# power-input.net
KiCad netlist of a schematic drawn in Altium Designer
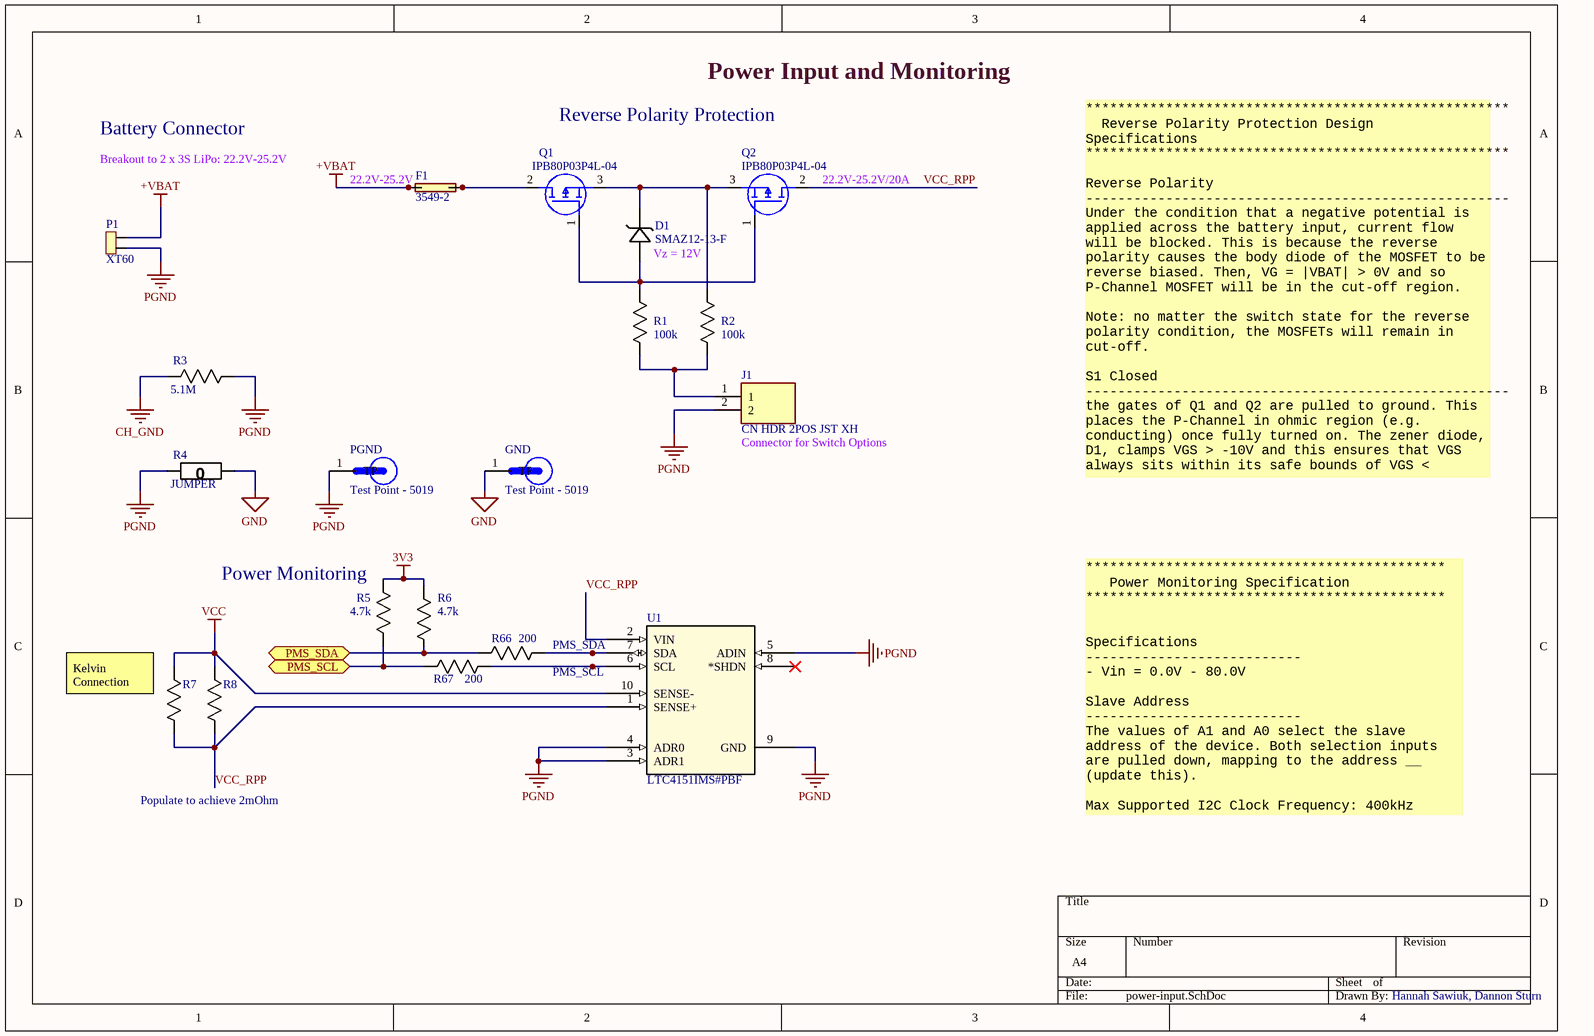
[diagram p0: power-input.SchDoc]

(export (version "E")
  (design (tool "Eeschema 10.0.6"))
  (components
    (comp (ref "D1")
      (value "SMAZ12-13-F")
      (footprint "SMA_DIO-L")
      (description "Zener Diode 12 V 1 W ±5% Surface Mount SMA")
      (fields (field (name "COPYRIGHT") "Copyright (C) 2021 Ultra Librarian. All rights reserved."))
      (libsource (lib "AltiumLibraries") (part "DIODE ZENER 12V 1W"))
    )
    (comp (ref "F1")
      (value "3549-2")
      (footprint "FUSE-3549-2")
      (description "Fuse Block 30A 500V 1 Circuit Blade Through Hole")
      (fields (field (name "MF") "Keystone Electronics") (field (name "MP") "3557-2"))
      (libsource (lib "AltiumLibraries") (part "FUSE BLADE"))
    )
    (comp (ref "GND")
      (value "Test Point - 5019")
      (footprint "TP380X203")
      (description "PC Test Point, Miniature Phosphor Bronze, Silver Plating Surface Mount Mounting Type")
      (fields (field (name "MP") "5019") (field (name "MF") "Keystone Electronics"))
      (libsource (lib "AltiumLibraries") (part "Test Point - 5019"))
    )
    (comp (ref "J1")
      (value "CN HDR 2POS JST XH")
      (footprint "JST_B2B-XH-A(LF)(SN)")
      (description "Connector Header Through Hole 2 position 0.098 _2.50mm_\r\nJST XH")
      (fields (field (name "MP") "B2B-XH-A_LF__SN_") (field (name "MF") "JST Sales"))
      (libsource (lib "AltiumLibraries") (part "CN HDR 2POS JST XH"))
    )
    (comp (ref "P1")
      (value "XT60")
      (footprint "Amass_XT60PW-M")
      (description "XT60 CONNECTORS FEMALE PAIR")
      (fields (field (name "MF") "SparkFun Electronics") (field (name "MP") "PRT-10474"))
      (libsource (lib "AltiumLibraries") (part "XT60 Connector"))
    )
    (comp (ref "PGND")
      (value "Test Point - 5019")
      (footprint "TP380X203")
      (description "PC Test Point, Miniature Phosphor Bronze, Silver Plating Surface Mount Mounting Type")
      (fields (field (name "MP") "5019") (field (name "MF") "Keystone Electronics"))
      (libsource (lib "AltiumLibraries") (part "Test Point - 5019"))
    )
    (comp (ref "PMS_SCL")
      (value "Test Point (Via)")
      (footprint "TP")
      (libsource (lib "AltiumLibraries") (part "Test Point (Via)"))
    )
    (comp (ref "PMS_SDA")
      (value "Test Point (Via)")
      (footprint "TP")
      (libsource (lib "AltiumLibraries") (part "Test Point (Via)"))
    )
    (comp (ref "Q1")
      (value "IPB80P03P4L-04")
      (footprint "IPB80P03P4L04")
      (description "P-Channel 30 V 80A (Tc) 137W (Tc) Surface Mount PG-TO263-3-2")
      (fields (field (name "MOUSER PART NUMBER") "726-IPB80P03P4L-04"))
      (libsource (lib "AltiumLibraries") (part "MOSFET IPB80P03P4L-04"))
    )
    (comp (ref "Q2")
      (value "IPB80P03P4L-04")
      (footprint "IPB80P03P4L04")
      (description "P-Channel 30 V 80A (Tc) 137W (Tc) Surface Mount PG-TO263-3-2")
      (fields (field (name "MOUSER PART NUMBER") "726-IPB80P03P4L-04"))
      (libsource (lib "AltiumLibraries") (part "MOSFET IPB80P03P4L-04"))
    )
    (comp (ref "R1")
      (value "100k")
      (footprint "0603")
      (description "RES SMD 100K OHM 1% 1/8W 0805/0603")
      (fields (field (name "TOLERANCE") "1%"))
      (libsource (lib "AltiumLibraries") (part "RES 100k 1/8W - 1%"))
    )
    (comp (ref "R2")
      (value "100k")
      (footprint "0603")
      (description "RES SMD 100K OHM 1% 1/8W 0805/0603")
      (fields (field (name "TOLERANCE") "1%"))
      (libsource (lib "AltiumLibraries") (part "RES 100k 1/8W - 1%"))
    )
    (comp (ref "R3")
      (value "5.1M")
      (footprint "0603")
      (description "RES SMD 5.1 MOHM 5% 1/8W 0805")
      (fields (field (name "TOLERANCE") "5%"))
      (libsource (lib "AltiumLibraries") (part "RES 5.1M 1/8W-5%"))
    )
    (comp (ref "R4")
      (value "JUMPER")
      (footprint "0603")
      (description "RES SMD 0 OHM JUMPER GENERIC 0805/0603")
      (libsource (lib "AltiumLibraries") (part "RES 0 JUMPER"))
    )
    (comp (ref "R5")
      (value "4.7k")
      (footprint "0603")
      (description "RES SMD 4.7k OHM 5% 1/8W 0805")
      (fields (field (name "TOLERANCE") "5%"))
      (libsource (lib "AltiumLibraries") (part "RES 4.7k 1/8W - 5%"))
    )
    (comp (ref "R6")
      (value "4.7k")
      (footprint "0603")
      (description "RES SMD 4.7k OHM 5% 1/8W 0805")
      (fields (field (name "TOLERANCE") "5%"))
      (libsource (lib "") (part "RES 4.7k 1/8W - 5%_1"))
    )
    (comp (ref "R7")
      (value "2mOHM")
      (footprint "2512")
      (description "RES SMD 2m OHM 1% 1W 1206")
      (fields (field (name "TOLERANCE") "1%"))
      (libsource (lib "AltiumLibraries") (part "RES 2m 1W"))
    )
    (comp (ref "R8")
      (value "2mOHM")
      (footprint "2512")
      (description "RES SMD 2m OHM 1% 1W 1206")
      (fields (field (name "TOLERANCE") "1%"))
      (libsource (lib "AltiumLibraries") (part "RES 2m 1W"))
    )
    (comp (ref "R66")
      (value "200")
      (footprint "0603")
      (description "RES SMD 200 OHM 5% 1/8W 0805")
      (fields (field (name "TOLERANCE") "5%"))
      (libsource (lib "AltiumLibraries") (part "RES 200.0 1/8W"))
    )
    (comp (ref "R67")
      (value "200")
      (footprint "0603")
      (description "RES SMD 200 OHM 5% 1/8W 0805")
      (fields (field (name "TOLERANCE") "5%"))
      (libsource (lib "AltiumLibraries") (part "RES 200.0 1/8W"))
    )
    (comp (ref "U1")
      (value "LTC4151IMS#PBF")
      (footprint "MSOP-10_MS_LIT")
      (description "Power Supply Controller Power Supply Monitor 10-MSOP")
      (fields
        (field (name "MANUFACTURER_PART_NUMBER") "ltc4151ims#pbf")
        (field (name "COPYRIGHT") "Copyright (C) 2021 Ultra Librarian. All rights reserved.")
      )
      (libsource (lib "AltiumLibraries") (part "ltc4151ims#pbf"))
    )
  )
  (nets
    (net (code "1") (name "+VBAT") (class "Default")
      (node (ref "F1") (pin "3") (pinfunction "2A_3") (pintype "passive"))
      (node (ref "F1") (pin "4") (pinfunction "2B_4") (pintype "passive"))
      (node (ref "P1") (pin "2") (pinfunction "2_2") (pintype "passive"))
    )
    (net (code "2") (name "/PMS_SCL") (class "Default")
      (node (ref "R5") (pin "1") (pinfunction "R1_1") (pintype "passive"))
      (node (ref "R67") (pin "2") (pinfunction "R2_2") (pintype "passive"))
    )
    (net (code "3") (name "/PMS_SDA") (class "Default")
      (node (ref "R6") (pin "1") (pinfunction "R1_1") (pintype "passive"))
      (node (ref "R66") (pin "2") (pinfunction "R2_2") (pintype "passive"))
    )
    (net (code "4") (name "/VCC_RPP") (class "Default")
      (node (ref "Q2") (pin "2") (pinfunction "D_2") (pintype "passive"))
      (node (ref "R7") (pin "2") (pinfunction "R2_2") (pintype "passive"))
      (node (ref "R8") (pin "2") (pinfunction "R2_2") (pintype "passive"))
      (node (ref "U1") (pin "1") (pinfunction "SENSE+_1") (pintype "input"))
      (node (ref "U1") (pin "2") (pinfunction "VIN_2") (pintype "input"))
    )
    (net (code "5") (name "3V3") (class "Default")
      (node (ref "R5") (pin "2") (pinfunction "R2_2") (pintype "passive"))
      (node (ref "R6") (pin "2") (pinfunction "R2_2") (pintype "passive"))
    )
    (net (code "6") (name "CH_GND") (class "Default")
      (node (ref "R3") (pin "2") (pinfunction "R2_2") (pintype "passive"))
    )
    (net (code "7") (name "GND") (class "Default")
      (node (ref "GND") (pin "1") (pinfunction "TP_1") (pintype "passive"))
      (node (ref "R4") (pin "1") (pinfunction "R1_1") (pintype "passive"))
    )
    (net (code "8") (name "Net-(F1-1A)") (class "Default")
      (node (ref "F1") (pin "1") (pinfunction "1A_1") (pintype "passive"))
      (node (ref "F1") (pin "2") (pinfunction "1B_2") (pintype "passive"))
      (node (ref "Q1") (pin "2") (pinfunction "D_2") (pintype "passive"))
    )
    (net (code "9") (name "Net-(Q1-G)") (class "Default")
      (node (ref "D1") (pin "2") (pinfunction "2_2") (pintype "passive"))
      (node (ref "Q1") (pin "1") (pinfunction "G_1") (pintype "passive"))
      (node (ref "Q2") (pin "1") (pinfunction "G_1") (pintype "passive"))
      (node (ref "R1") (pin "1") (pinfunction "R1_1") (pintype "passive"))
    )
    (net (code "10") (name "Net-(Q1-S)") (class "Default")
      (node (ref "D1") (pin "1") (pinfunction "1_1") (pintype "passive"))
      (node (ref "Q1") (pin "3") (pinfunction "S_3") (pintype "passive"))
      (node (ref "Q2") (pin "3") (pinfunction "S_3") (pintype "passive"))
      (node (ref "R2") (pin "1") (pinfunction "R1_1") (pintype "passive"))
    )
    (net (code "11") (name "Net-(R1-R2)") (class "Default")
      (node (ref "J1") (pin "1") (pinfunction "1_1") (pintype "passive"))
      (node (ref "R1") (pin "2") (pinfunction "R2_2") (pintype "passive"))
      (node (ref "R2") (pin "2") (pinfunction "R2_2") (pintype "passive"))
    )
    (net (code "12") (name "Net-(R66-R1)") (class "Default")
      (node (ref "PMS_SDA") (pin "1") (pinfunction "1_1") (pintype "passive"))
      (node (ref "R66") (pin "1") (pinfunction "R1_1") (pintype "passive"))
      (node (ref "U1") (pin "7") (pinfunction "SDA_7") (pintype "bidirectional"))
    )
    (net (code "13") (name "Net-(R67-R1)") (class "Default")
      (node (ref "PMS_SCL") (pin "1") (pinfunction "1_1") (pintype "passive"))
      (node (ref "R67") (pin "1") (pinfunction "R1_1") (pintype "passive"))
      (node (ref "U1") (pin "6") (pinfunction "SCL_6") (pintype "input"))
    )
    (net (code "14") (name "PGND") (class "Default")
      (node (ref "J1") (pin "2") (pinfunction "2_2") (pintype "passive"))
      (node (ref "P1") (pin "1") (pinfunction "1_1") (pintype "passive"))
      (node (ref "PGND") (pin "1") (pinfunction "TP_1") (pintype "passive"))
      (node (ref "R3") (pin "1") (pinfunction "R1_1") (pintype "passive"))
      (node (ref "R4") (pin "2") (pinfunction "R2_2") (pintype "passive"))
      (node (ref "U1") (pin "3") (pinfunction "ADR1_3") (pintype "input"))
      (node (ref "U1") (pin "4") (pinfunction "ADR0_4") (pintype "input"))
      (node (ref "U1") (pin "5") (pinfunction "ADIN_5") (pintype "input"))
      (node (ref "U1") (pin "9") (pinfunction "GND_9") (pintype "power_in"))
    )
    (net (code "15") (name "VCC") (class "Default")
      (node (ref "R7") (pin "1") (pinfunction "R1_1") (pintype "passive"))
      (node (ref "R8") (pin "1") (pinfunction "R1_1") (pintype "passive"))
      (node (ref "U1") (pin "10") (pinfunction "SENSE-_10") (pintype "input"))
    )
    (net (code "16") (name "unconnected-(U1-*SHDN-Pad8)") (class "Default")
      (node (ref "U1") (pin "8") (pinfunction "*SHDN_8") (pintype "input+no_connect"))
    )
  )
)
